# untitled.net
KiCad netlist of a schematic drawn in EAGLE
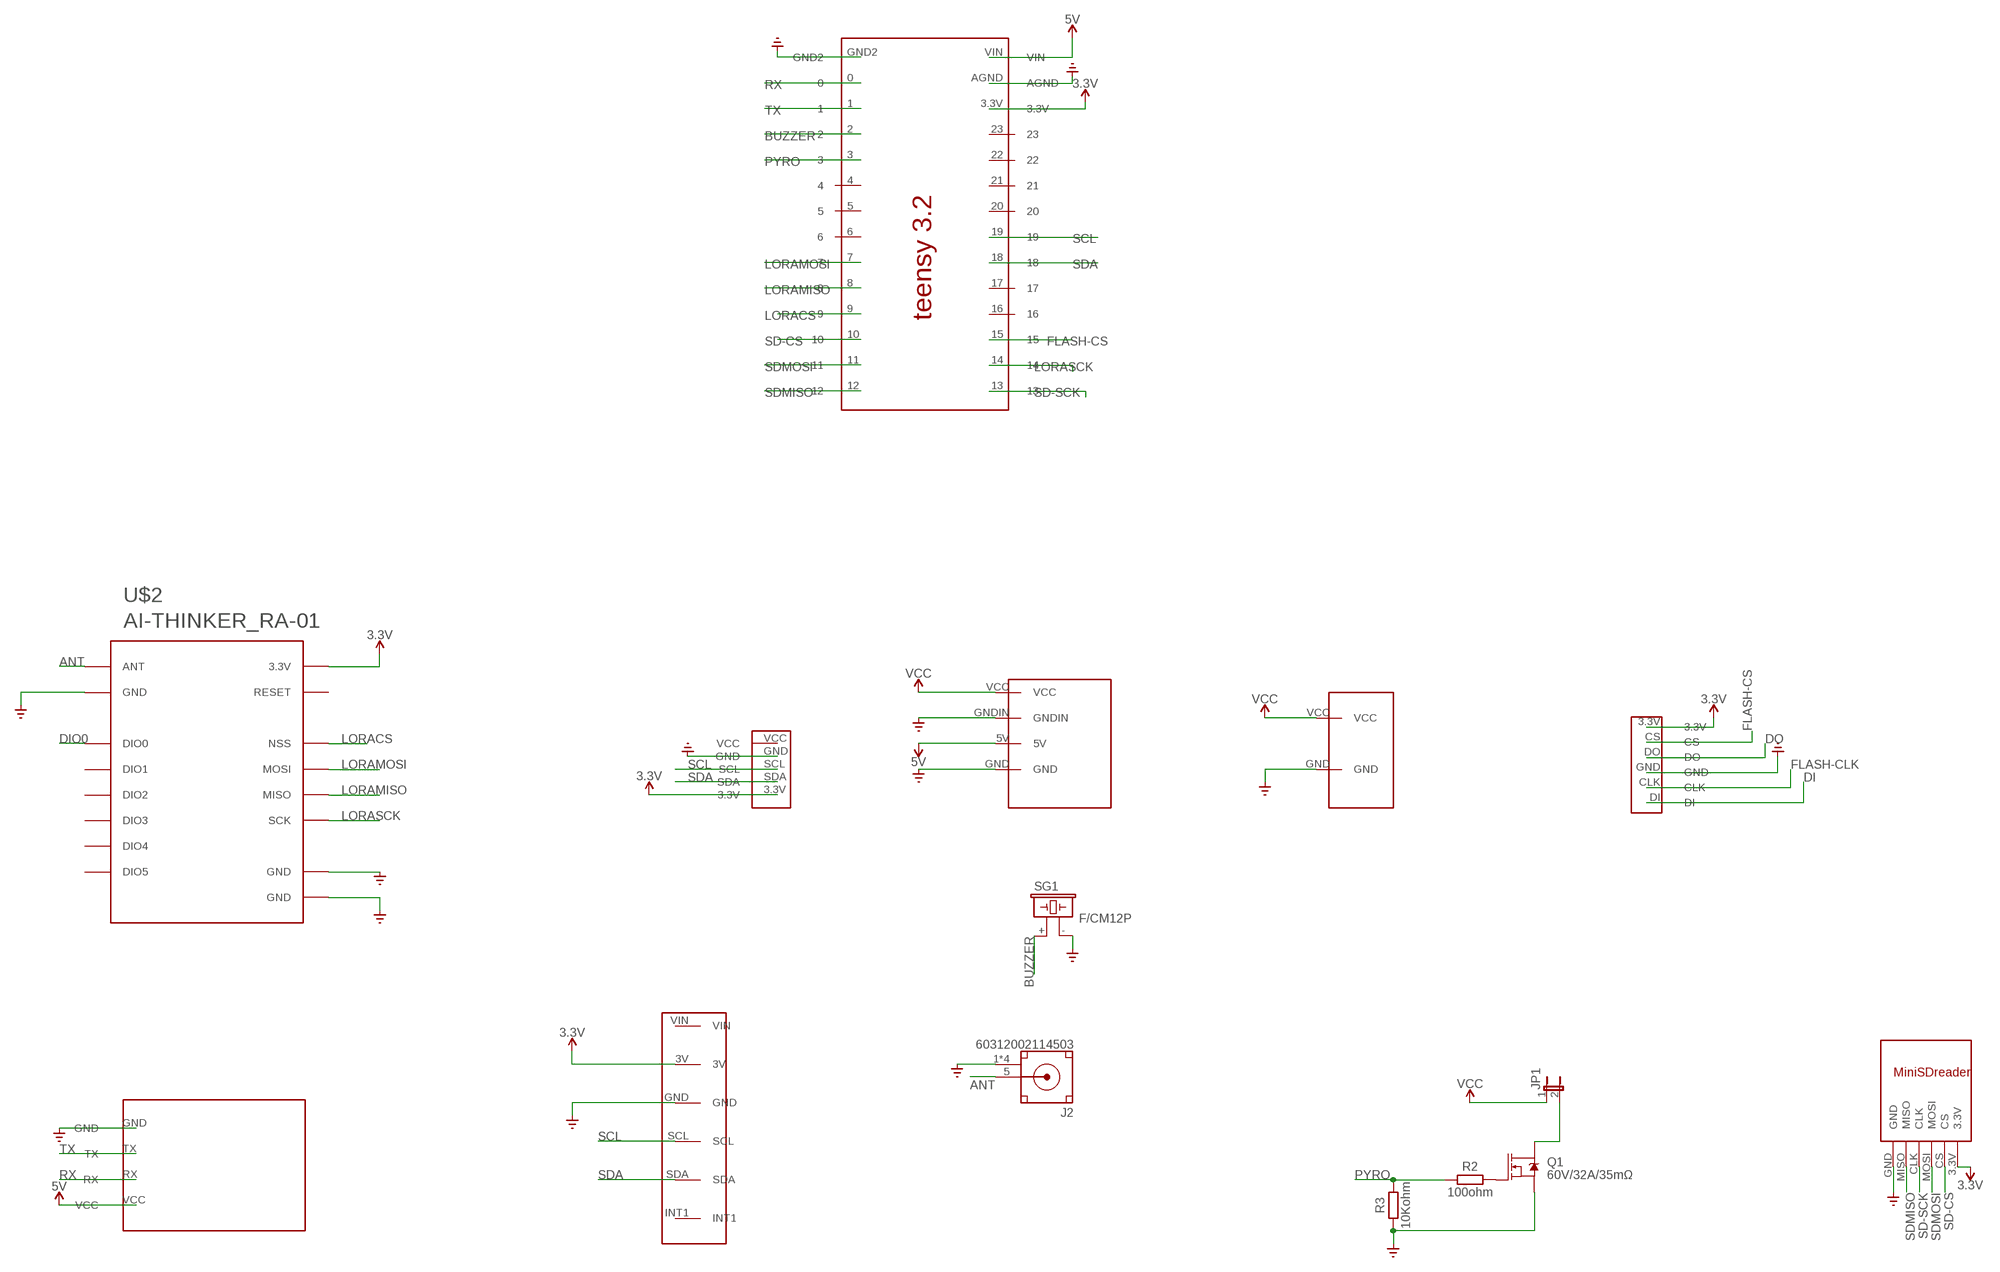
[diagram p0: schematic, sheet 1]

(export (version "E")
  (design (tool "Eeschema 10.0.6"))
  (components
    (comp (ref "J2")
      (value "60312002114503")
      (footprint "eagle-import:60312002114503")
      (fields
        (field (name "DIGIKEY_PART_NUMBER") "732-13835-ND")
        (field (name "MANUFACTURER") "Wurth Electronics Inc.")
        (field (name "CREATED_BY") "PCBLayout.com")
      )
      (libsource (lib "eagle-import") (part "60312002114503"))
    )
    (comp (ref "JP1")
      (value "JP1E")
      (footprint "eagle-import:JP1")
      (libsource (lib "eagle-import") (part "JP1E"))
    )
    (comp (ref "Q1")
      (value "60V/32A/35mΩ")
      (footprint "eagle-import:TO220V")
      (libsource (lib "eagle-import") (part "MOSFET-NCH-FQP30N06L"))
    )
    (comp (ref "R2")
      (value "100ohm")
      (footprint "eagle-import:RESAD724W46L381D178B")
      (libsource (lib "eagle-import") (part "RAXIAL-7.2MM-PITCH_"))
    )
    (comp (ref "R3")
      (value "10Kohm")
      (footprint "eagle-import:RESAD724W46L381D178B")
      (libsource (lib "eagle-import") (part "RAXIAL-7.2MM-PITCH_"))
    )
    (comp (ref "SG1")
      (value "F/CM12P")
      (footprint "eagle-import:F_CM12P")
      (libsource (lib "eagle-import") (part "F/CM12P"))
    )
    (comp (ref "U$1")
      (value "TEENSY3.2")
      (footprint "eagle-import:TEENSY3.2")
      (libsource (lib "eagle-import") (part "TEENSY3.2"))
    )
    (comp (ref "U$2")
      (value "AI-THINKER_RA-01")
      (footprint "eagle-import:AI-THINKER_RA-01")
      (libsource (lib "eagle-import") (part "AI-THINKER_RA-01"))
    )
    (comp (ref "U$3")
      (value "BMP180")
      (footprint "eagle-import:BMP180")
      (libsource (lib "eagle-import") (part "BMP180"))
    )
    (comp (ref "U$4")
      (value "NEO-M8NGPSMODULE")
      (footprint "eagle-import:NEO-M8NGPSMODULE")
      (libsource (lib "eagle-import") (part "NEO-M8NGPSMODULE"))
    )
    (comp (ref "U$5")
      (value "ICM20649")
      (footprint "eagle-import:ICM20649")
      (libsource (lib "eagle-import") (part "ICM20649"))
    )
    (comp (ref "U$6")
      (value "FLASH")
      (footprint "eagle-import:FLASH")
      (libsource (lib "eagle-import") (part "FLASH"))
    )
    (comp (ref "U$7")
      (value "MINISDREADER")
      (footprint "eagle-import:MINISDREADER")
      (libsource (lib "eagle-import") (part "MINISDREADER"))
    )
    (comp (ref "U$8")
      (value "BATT")
      (footprint "eagle-import:BATT")
      (libsource (lib "eagle-import") (part "BATT"))
    )
    (comp (ref "U$9")
      (value "VREG")
      (footprint "eagle-import:VREG")
      (libsource (lib "eagle-import") (part "VREG"))
    )
  )
  (nets
    (net (code "1") (name "/ANT") (class "Default")
      (node (ref "J2") (pin "5") (pinfunction "SIGNAL_5") (pintype "passive"))
      (node (ref "U$2") (pin "P$1") (pinfunction "ANT_P$1") (pintype "bidirectional"))
    )
    (net (code "2") (name "/BUZZER") (class "Default")
      (node (ref "SG1") (pin "+") (pinfunction "1_+") (pintype "passive"))
      (node (ref "U$1") (pin "2") (pinfunction "2_2") (pintype "bidirectional"))
    )
    (net (code "3") (name "/DI") (class "Default")
      (node (ref "U$6") (pin "DI") (pinfunction "DI_DI") (pintype "bidirectional"))
    )
    (net (code "4") (name "/DIO0") (class "Default")
      (node (ref "U$2") (pin "P$5") (pinfunction "DIO0_P$5") (pintype "bidirectional"))
    )
    (net (code "5") (name "/DO") (class "Default")
      (node (ref "U$6") (pin "DO") (pinfunction "DO_DO") (pintype "bidirectional"))
    )
    (net (code "6") (name "/FLASH-CLK") (class "Default")
      (node (ref "U$6") (pin "CLK") (pinfunction "CLK_CLK") (pintype "bidirectional"))
    )
    (net (code "7") (name "/FLASH-CS") (class "Default")
      (node (ref "U$1") (pin "15") (pinfunction "15_15") (pintype "bidirectional"))
      (node (ref "U$6") (pin "CS") (pinfunction "CS_CS") (pintype "bidirectional"))
    )
    (net (code "8") (name "/LORACS") (class "Default")
      (node (ref "U$1") (pin "9") (pinfunction "9_9") (pintype "bidirectional"))
      (node (ref "U$2") (pin "P$15") (pinfunction "NSS_P$15") (pintype "bidirectional"))
    )
    (net (code "9") (name "/LORAMISO") (class "Default")
      (node (ref "U$1") (pin "8") (pinfunction "8_8") (pintype "bidirectional"))
      (node (ref "U$2") (pin "P$13") (pinfunction "MISO_P$13") (pintype "bidirectional"))
    )
    (net (code "10") (name "/LORAMOSI") (class "Default")
      (node (ref "U$1") (pin "7") (pinfunction "7_7") (pintype "bidirectional"))
      (node (ref "U$2") (pin "P$14") (pinfunction "MOSI_P$14") (pintype "bidirectional"))
    )
    (net (code "11") (name "/LORASCK") (class "Default")
      (node (ref "U$1") (pin "14") (pinfunction "14_14") (pintype "bidirectional"))
      (node (ref "U$2") (pin "P$12") (pinfunction "SCK_P$12") (pintype "bidirectional"))
    )
    (net (code "12") (name "/PYRO") (class "Default")
      (node (ref "R2") (pin "1") (pinfunction "1_1") (pintype "passive"))
      (node (ref "R3") (pin "2") (pinfunction "2_2") (pintype "passive"))
      (node (ref "U$1") (pin "3") (pinfunction "3_3") (pintype "bidirectional"))
    )
    (net (code "13") (name "/RX") (class "Default")
      (node (ref "U$1") (pin "0") (pinfunction "0_0") (pintype "bidirectional"))
      (node (ref "U$4") (pin "RX") (pinfunction "RX_RX") (pintype "bidirectional"))
    )
    (net (code "14") (name "/SCL") (class "Default")
      (node (ref "U$1") (pin "19") (pinfunction "19_19") (pintype "bidirectional"))
      (node (ref "U$3") (pin "SCL") (pinfunction "SCL_SCL") (pintype "bidirectional"))
      (node (ref "U$5") (pin "SCL") (pinfunction "SCL_SCL") (pintype "bidirectional"))
    )
    (net (code "15") (name "/SD-CS") (class "Default")
      (node (ref "U$1") (pin "10") (pinfunction "10_10") (pintype "bidirectional"))
      (node (ref "U$7") (pin "CS") (pinfunction "CS_CS") (pintype "bidirectional"))
    )
    (net (code "16") (name "/SD-SCK") (class "Default")
      (node (ref "U$1") (pin "13") (pinfunction "13_13") (pintype "bidirectional"))
      (node (ref "U$7") (pin "CLK") (pinfunction "CLK_CLK") (pintype "bidirectional"))
    )
    (net (code "17") (name "/SDA") (class "Default")
      (node (ref "U$1") (pin "18") (pinfunction "18_18") (pintype "bidirectional"))
      (node (ref "U$3") (pin "SDA") (pinfunction "SDA_SDA") (pintype "bidirectional"))
      (node (ref "U$5") (pin "SDA") (pinfunction "SDA_SDA") (pintype "bidirectional"))
    )
    (net (code "18") (name "/SDMISO") (class "Default")
      (node (ref "U$1") (pin "12") (pinfunction "12_12") (pintype "bidirectional"))
      (node (ref "U$7") (pin "MISO") (pinfunction "MISO_MISO") (pintype "bidirectional"))
    )
    (net (code "19") (name "/SDMOSI") (class "Default")
      (node (ref "U$1") (pin "11") (pinfunction "11_11") (pintype "bidirectional"))
      (node (ref "U$7") (pin "MOSI") (pinfunction "MOSI_MOSI") (pintype "bidirectional"))
    )
    (net (code "20") (name "/TX") (class "Default")
      (node (ref "U$1") (pin "1") (pinfunction "1_1") (pintype "bidirectional"))
      (node (ref "U$4") (pin "TX") (pinfunction "TX_TX") (pintype "bidirectional"))
    )
    (net (code "21") (name "3.3V") (class "Default")
      (node (ref "U$1") (pin "3.3V") (pinfunction "3.3V_3.3V") (pintype "bidirectional"))
      (node (ref "U$2") (pin "P$3") (pinfunction "3.3V_P$3") (pintype "bidirectional"))
      (node (ref "U$3") (pin "3.3V") (pinfunction "3.3V_3.3V") (pintype "bidirectional"))
      (node (ref "U$5") (pin "3V") (pinfunction "3V_3V") (pintype "bidirectional"))
      (node (ref "U$6") (pin "3.3V") (pinfunction "3.3V_3.3V") (pintype "bidirectional"))
      (node (ref "U$7") (pin "3.3V") (pinfunction "3.3V_3.3V") (pintype "bidirectional"))
    )
    (net (code "22") (name "5V") (class "Default")
      (node (ref "U$1") (pin "VIN") (pinfunction "VIN_VIN") (pintype "bidirectional"))
      (node (ref "U$4") (pin "VCC") (pinfunction "VCC_VCC") (pintype "bidirectional"))
      (node (ref "U$9") (pin "5V") (pinfunction "5V_5V") (pintype "bidirectional"))
    )
    (net (code "23") (name "Net-(Q1-D)") (class "Default")
      (node (ref "JP1") (pin "2") (pinfunction "2_2") (pintype "passive"))
      (node (ref "Q1") (pin "2") (pinfunction "D_2") (pintype "bidirectional"))
    )
    (net (code "24") (name "Net-(Q1-G)") (class "Default")
      (node (ref "Q1") (pin "1") (pinfunction "G_1") (pintype "bidirectional"))
      (node (ref "R2") (pin "2") (pinfunction "2_2") (pintype "passive"))
    )
    (net (code "25") (name "SUPPLY0_GND_") (class "Default")
      (node (ref "J2") (pin "1") (pinfunction "GND_1") (pintype "power_in"))
      (node (ref "J2") (pin "2") (pinfunction "GND_2") (pintype "power_in"))
      (node (ref "J2") (pin "3") (pinfunction "GND_3") (pintype "power_in"))
      (node (ref "J2") (pin "4") (pinfunction "GND_4") (pintype "power_in"))
      (node (ref "Q1") (pin "3") (pinfunction "S_3") (pintype "bidirectional"))
      (node (ref "R3") (pin "1") (pinfunction "1_1") (pintype "passive"))
      (node (ref "SG1") (pin "-") (pinfunction "2_-") (pintype "passive"))
      (node (ref "U$1") (pin "AGND") (pinfunction "AGND_AGND") (pintype "bidirectional"))
      (node (ref "U$1") (pin "GND2") (pinfunction "GND2_GND2") (pintype "bidirectional"))
      (node (ref "U$2") (pin "P$16") (pinfunction "GND_P$16") (pintype "bidirectional"))
      (node (ref "U$2") (pin "P$2") (pinfunction "GND_P$2") (pintype "bidirectional"))
      (node (ref "U$2") (pin "P$9") (pinfunction "GND_P$9") (pintype "bidirectional"))
      (node (ref "U$3") (pin "GND") (pinfunction "GND_GND") (pintype "bidirectional"))
      (node (ref "U$4") (pin "GND") (pinfunction "GND_GND") (pintype "bidirectional"))
      (node (ref "U$5") (pin "GND") (pinfunction "GND_GND") (pintype "bidirectional"))
      (node (ref "U$6") (pin "GND") (pinfunction "GND_GND") (pintype "bidirectional"))
      (node (ref "U$7") (pin "GND") (pinfunction "GND_GND") (pintype "bidirectional"))
      (node (ref "U$8") (pin "GND") (pinfunction "GND_GND") (pintype "bidirectional"))
      (node (ref "U$9") (pin "GND") (pinfunction "GND_GND") (pintype "bidirectional"))
      (node (ref "U$9") (pin "GNDIN") (pinfunction "GNDIN_GNDIN") (pintype "bidirectional"))
    )
    (net (code "26") (name "VCC") (class "Default")
      (node (ref "JP1") (pin "1") (pinfunction "1_1") (pintype "passive"))
      (node (ref "U$8") (pin "VCC") (pinfunction "VCC_VCC") (pintype "bidirectional"))
      (node (ref "U$9") (pin "VCC") (pinfunction "VCC_VCC") (pintype "bidirectional"))
    )
    (net (code "27") (name "unconnected-(U$1-Pad4)") (class "Default")
      (node (ref "U$1") (pin "4") (pinfunction "4_4") (pintype "bidirectional"))
    )
    (net (code "28") (name "unconnected-(U$1-Pad5)") (class "Default")
      (node (ref "U$1") (pin "5") (pinfunction "5_5") (pintype "bidirectional"))
    )
    (net (code "29") (name "unconnected-(U$1-Pad6)") (class "Default")
      (node (ref "U$1") (pin "6") (pinfunction "6_6") (pintype "bidirectional"))
    )
    (net (code "30") (name "unconnected-(U$1-Pad16)") (class "Default")
      (node (ref "U$1") (pin "16") (pinfunction "16_16") (pintype "bidirectional"))
    )
    (net (code "31") (name "unconnected-(U$1-Pad17)") (class "Default")
      (node (ref "U$1") (pin "17") (pinfunction "17_17") (pintype "bidirectional"))
    )
    (net (code "32") (name "unconnected-(U$1-Pad20)") (class "Default")
      (node (ref "U$1") (pin "20") (pinfunction "20_20") (pintype "bidirectional"))
    )
    (net (code "33") (name "unconnected-(U$1-Pad21)") (class "Default")
      (node (ref "U$1") (pin "21") (pinfunction "21_21") (pintype "bidirectional"))
    )
    (net (code "34") (name "unconnected-(U$1-Pad22)") (class "Default")
      (node (ref "U$1") (pin "22") (pinfunction "22_22") (pintype "bidirectional"))
    )
    (net (code "35") (name "unconnected-(U$1-Pad23)") (class "Default")
      (node (ref "U$1") (pin "23") (pinfunction "23_23") (pintype "bidirectional"))
    )
    (net (code "36") (name "unconnected-(U$2-DIO1-PadP$6)") (class "Default")
      (node (ref "U$2") (pin "P$6") (pinfunction "DIO1_P$6") (pintype "bidirectional"))
    )
    (net (code "37") (name "unconnected-(U$2-DIO2-PadP$7)") (class "Default")
      (node (ref "U$2") (pin "P$7") (pinfunction "DIO2_P$7") (pintype "bidirectional"))
    )
    (net (code "38") (name "unconnected-(U$2-DIO3-PadP$8)") (class "Default")
      (node (ref "U$2") (pin "P$8") (pinfunction "DIO3_P$8") (pintype "bidirectional"))
    )
    (net (code "39") (name "unconnected-(U$2-DIO4-PadP$10)") (class "Default")
      (node (ref "U$2") (pin "P$10") (pinfunction "DIO4_P$10") (pintype "bidirectional"))
    )
    (net (code "40") (name "unconnected-(U$2-DIO5-PadP$11)") (class "Default")
      (node (ref "U$2") (pin "P$11") (pinfunction "DIO5_P$11") (pintype "bidirectional"))
    )
    (net (code "41") (name "unconnected-(U$2-RESET-PadP$4)") (class "Default")
      (node (ref "U$2") (pin "P$4") (pinfunction "RESET_P$4") (pintype "bidirectional"))
    )
    (net (code "42") (name "unconnected-(U$3-PadVCC)") (class "Default")
      (node (ref "U$3") (pin "VCC") (pinfunction "VCC_VCC") (pintype "bidirectional"))
    )
    (net (code "43") (name "unconnected-(U$5-PadINT1)") (class "Default")
      (node (ref "U$5") (pin "INT1") (pinfunction "INT1_INT1") (pintype "bidirectional"))
    )
    (net (code "44") (name "unconnected-(U$5-PadVIN)") (class "Default")
      (node (ref "U$5") (pin "VIN") (pinfunction "VIN_VIN") (pintype "bidirectional"))
    )
  )
)
